# usb_host_slave.net
KiCad netlist of a schematic drawn in Altium Designer
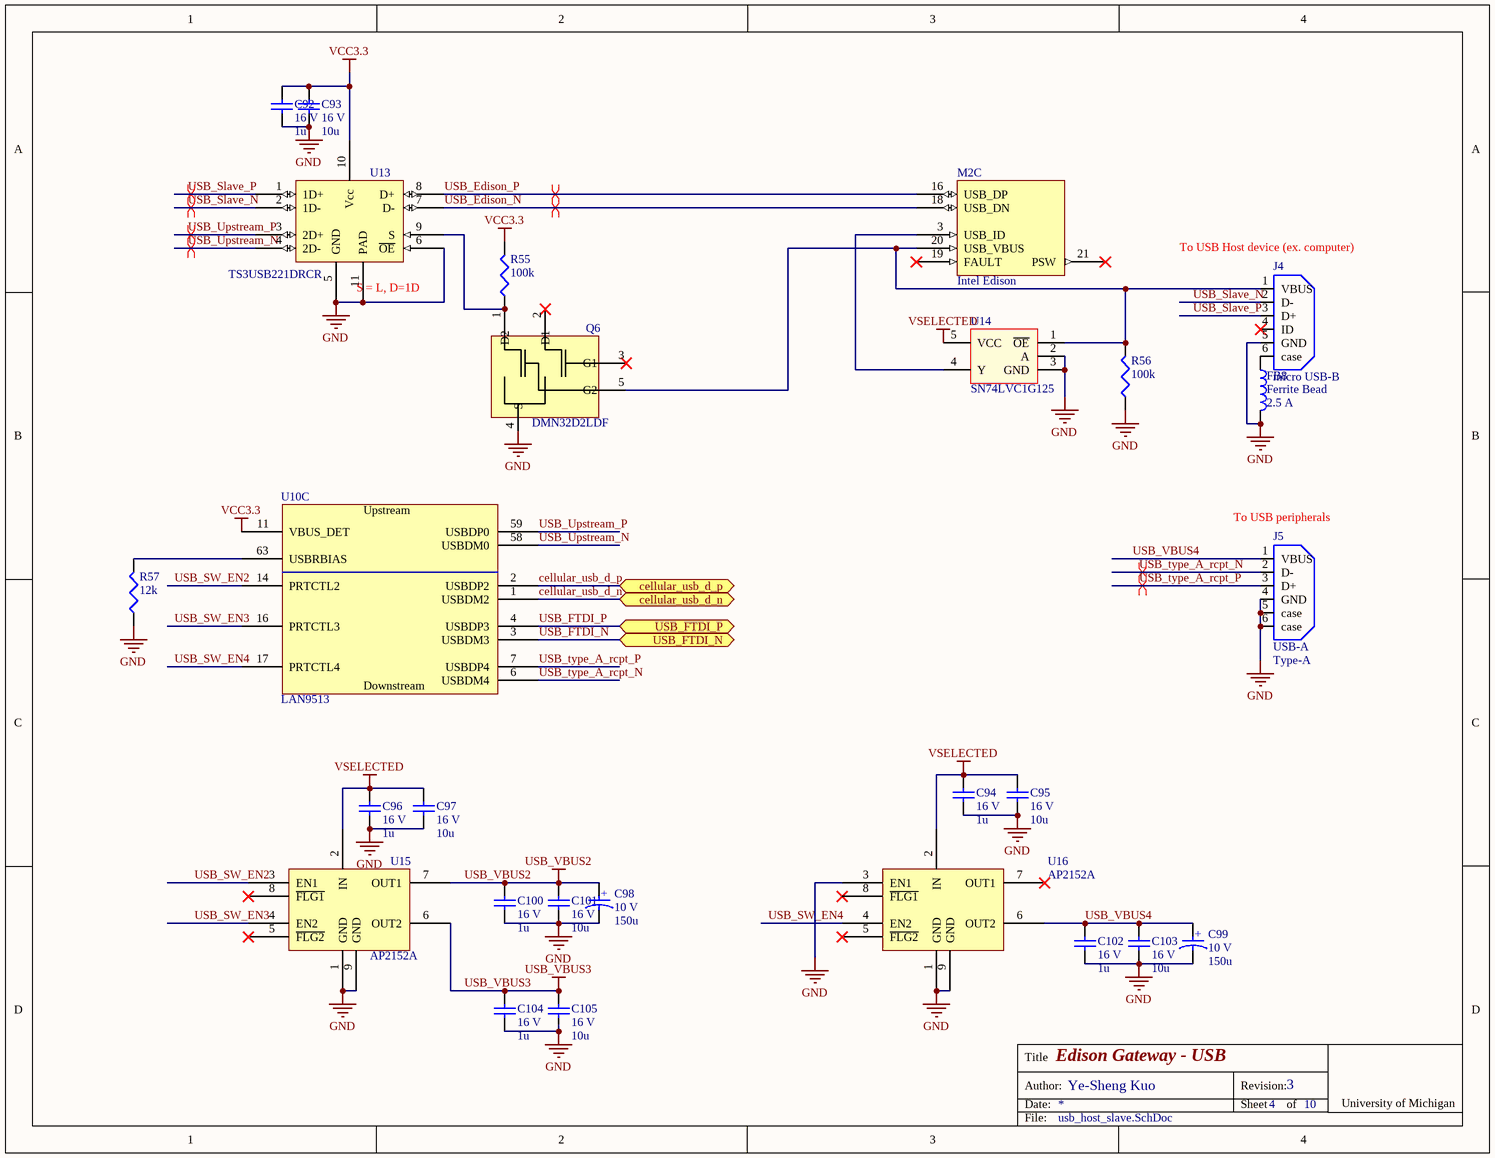
[diagram p0: usb_host_slave.SchDoc]

(export (version "E")
  (design (tool "Eeschema 10.0.6"))
  (components
    (comp (ref "C92")
      (value "1u")
      (footprint "0402")
      (description "1µF ±10% 16V Ceramic Capacitor X6S 0402")
      (fields
        (field (name "VOLTAGE RATED") "16 V")
        (field (name "TOLERANCE") "10%")
        (field (name "MANUFACTURER PART NUMBER") "C1005X6S1C105K050BC")
      )
      (libsource (lib "capacitors") (part "C1005X6S1C105K050BC"))
    )
    (comp (ref "C93")
      (value "10u")
      (footprint "0603")
      (description "10µF ±20% 16V Ceramic Capacitor X6S 0603")
      (fields
        (field (name "TOLERANCE") "20%")
        (field (name "VOLTAGE RATED") "16 V")
        (field (name "MANUFACTURER PART NUMBER") "GRM188C81C106MA73D")
      )
      (libsource (lib "capacitors") (part "GRM188C81C106MA73D"))
    )
    (comp (ref "C94")
      (value "1u")
      (footprint "0402")
      (description "1µF ±10% 16V Ceramic Capacitor X6S 0402")
      (fields
        (field (name "VOLTAGE RATED") "16 V")
        (field (name "TOLERANCE") "10%")
        (field (name "MANUFACTURER PART NUMBER") "C1005X6S1C105K050BC")
      )
      (libsource (lib "capacitors") (part "C1005X6S1C105K050BC"))
    )
    (comp (ref "C95")
      (value "10u")
      (footprint "0603")
      (description "10µF ±20% 16V Ceramic Capacitor X6S 0603")
      (fields
        (field (name "TOLERANCE") "20%")
        (field (name "VOLTAGE RATED") "16 V")
        (field (name "MANUFACTURER PART NUMBER") "GRM188C81C106MA73D")
      )
      (libsource (lib "capacitors") (part "GRM188C81C106MA73D"))
    )
    (comp (ref "C96")
      (value "1u")
      (footprint "0402")
      (description "1µF ±10% 16V Ceramic Capacitor X6S 0402")
      (fields
        (field (name "VOLTAGE RATED") "16 V")
        (field (name "TOLERANCE") "10%")
        (field (name "MANUFACTURER PART NUMBER") "C1005X6S1C105K050BC")
      )
      (libsource (lib "capacitors") (part "C1005X6S1C105K050BC"))
    )
    (comp (ref "C97")
      (value "10u")
      (footprint "0603")
      (description "10µF ±20% 16V Ceramic Capacitor X6S 0603")
      (fields
        (field (name "TOLERANCE") "20%")
        (field (name "VOLTAGE RATED") "16 V")
        (field (name "MANUFACTURER PART NUMBER") "GRM188C81C106MA73D")
      )
      (libsource (lib "capacitors") (part "GRM188C81C106MA73D"))
    )
    (comp (ref "C98")
      (value "150u")
      (footprint "2312")
      (description "150µF ±10% Molded Tantalum Capacitors 10V 2312")
      (fields
        (field (name "TOLERANCE") "10%")
        (field (name "VOLTAGE RATED") "10 V")
        (field (name "MANUFACTURER PART NUMBER") "TAJC157K010RNJ")
      )
      (libsource (lib "capacitors") (part "TAJC157K010RNJ"))
    )
    (comp (ref "C99")
      (value "150u")
      (footprint "2312")
      (description "150µF ±10% Molded Tantalum Capacitors 10V 2312")
      (fields
        (field (name "TOLERANCE") "10%")
        (field (name "VOLTAGE RATED") "10 V")
        (field (name "MANUFACTURER PART NUMBER") "TAJC157K010RNJ")
      )
      (libsource (lib "capacitors") (part "TAJC157K010RNJ"))
    )
    (comp (ref "C100")
      (value "1u")
      (footprint "0402")
      (description "1µF ±10% 16V Ceramic Capacitor X6S 0402")
      (fields
        (field (name "VOLTAGE RATED") "16 V")
        (field (name "TOLERANCE") "10%")
        (field (name "MANUFACTURER PART NUMBER") "C1005X6S1C105K050BC")
      )
      (libsource (lib "capacitors") (part "C1005X6S1C105K050BC"))
    )
    (comp (ref "C101")
      (value "10u")
      (footprint "0603")
      (description "10µF ±20% 16V Ceramic Capacitor X6S 0603")
      (fields
        (field (name "TOLERANCE") "20%")
        (field (name "VOLTAGE RATED") "16 V")
        (field (name "MANUFACTURER PART NUMBER") "GRM188C81C106MA73D")
      )
      (libsource (lib "capacitors") (part "GRM188C81C106MA73D"))
    )
    (comp (ref "C102")
      (value "1u")
      (footprint "0402")
      (description "1µF ±10% 16V Ceramic Capacitor X6S 0402")
      (fields
        (field (name "VOLTAGE RATED") "16 V")
        (field (name "TOLERANCE") "10%")
        (field (name "MANUFACTURER PART NUMBER") "C1005X6S1C105K050BC")
      )
      (libsource (lib "capacitors") (part "C1005X6S1C105K050BC"))
    )
    (comp (ref "C103")
      (value "10u")
      (footprint "0603")
      (description "10µF ±20% 16V Ceramic Capacitor X6S 0603")
      (fields
        (field (name "TOLERANCE") "20%")
        (field (name "VOLTAGE RATED") "16 V")
        (field (name "MANUFACTURER PART NUMBER") "GRM188C81C106MA73D")
      )
      (libsource (lib "capacitors") (part "GRM188C81C106MA73D"))
    )
    (comp (ref "C104")
      (value "1u")
      (footprint "0402")
      (description "1µF ±10% 16V Ceramic Capacitor X6S 0402")
      (fields
        (field (name "VOLTAGE RATED") "16 V")
        (field (name "TOLERANCE") "10%")
        (field (name "MANUFACTURER PART NUMBER") "C1005X6S1C105K050BC")
      )
      (libsource (lib "capacitors") (part "C1005X6S1C105K050BC"))
    )
    (comp (ref "C105")
      (value "10u")
      (footprint "0603")
      (description "10µF ±20% 16V Ceramic Capacitor X6S 0603")
      (fields
        (field (name "TOLERANCE") "20%")
        (field (name "VOLTAGE RATED") "16 V")
        (field (name "MANUFACTURER PART NUMBER") "GRM188C81C106MA73D")
      )
      (libsource (lib "capacitors") (part "GRM188C81C106MA73D"))
    )
    (comp (ref "FB8")
      (value "Ferrite Bead")
      (footprint "0603")
      (description "FERRITE BEAD 220 OHM 0603")
      (fields
        (field (name "MANUFACTURER PART NUMBER") "BLM18SG221TN1D")
        (field (name "MANUFACTURER") "Murata")
        (field (name "CURRENT RATING (MAX)") "2.5 A")
      )
      (libsource (lib "ferrite_beads") (part "BLM18SG221TN1D"))
    )
    (comp (ref "J4")
      (value "micro USB-B")
      (footprint "Micro USB-B")
      (description "CONN USB MICRO B RECPT SMT R/A")
      (libsource (lib "connectors") (part "Micro USB"))
    )
    (comp (ref "J5")
      (value "USB-A")
      (footprint "292303-2")
      (description "USB 2.0 Type A")
      (fields (field (name "TYPE") "Type-A"))
      (libsource (lib "connectors") (part "A105221-ND"))
    )
    (comp (ref "M2")
      (value "Intel Edison")
      (footprint "Intel Edison mating")
      (libsource (lib "Intel Edison") (part "Intel Edison"))
    )
    (comp (ref "Q6")
      (value "DMN32D2LDF")
      (footprint "SOT-353-5")
      (description "Common Source Dual N-Channel MOSFET")
      (libsource (lib "transistors") (part "DMN32D2LDF"))
    )
    (comp (ref "R55")
      (value "100k")
      (footprint "0402")
      (description "RES SMD 100K OHM 1% 1/16W 0402")
      (fields (field (name "TOLERANCE") "1%") (field (name "POWER") "1/16 W"))
      (libsource (lib "resistors") (part "CRCW0402100KFKED"))
    )
    (comp (ref "R56")
      (value "100k")
      (footprint "0402")
      (description "RES SMD 100K OHM 1% 1/16W 0402")
      (fields (field (name "TOLERANCE") "1%") (field (name "POWER") "1/16 W"))
      (libsource (lib "resistors") (part "CRCW0402100KFKED"))
    )
    (comp (ref "R57")
      (value "12k")
      (footprint "0402")
      (description "RES SMD 12K OHM 1% 1/16W 0402")
      (fields (field (name "TOLERANCE") "1%") (field (name "POWER") "1/16 W"))
      (libsource (lib "resistors") (part "CRCW040212K0FKED"))
    )
    (comp (ref "U10")
      (value "LAN9513")
      (footprint "QFN-64")
      (description "USB 2.0 Hub and 10/100  Ethernet Controller")
      (libsource (lib "ethernet controller") (part "LAN9513"))
    )
    (comp (ref "U13")
      (value "TS3USB221DRCR")
      (footprint "S-PVSON-N10")
      (description "High-Speed USB 2.0 (480-Mbps) 1:2 Multiplexer – Demultiplexer  Switch With Single Enable")
      (libsource (lib "multiplexer") (part "TS3USB221DRCR"))
    )
    (comp (ref "U14")
      (value "SN74LVC1G125")
      (footprint "SOT23-5")
      (description "Single Bus Buffer Gate With 3-State Output")
      (libsource (lib "logics") (part "SN74LVC1G125"))
    )
    (comp (ref "U15")
      (value "AP2152A")
      (footprint "U-DFN3030-8")
      (description "0.5A DUAL CHANNEL CURRENT-LIMITED  POWER SWITCH WITH OUTPUT DISCHARGE")
      (libsource (lib "load switch") (part "AP2152A"))
    )
    (comp (ref "U16")
      (value "AP2152A")
      (footprint "U-DFN3030-8")
      (description "0.5A DUAL CHANNEL CURRENT-LIMITED  POWER SWITCH WITH OUTPUT DISCHARGE")
      (libsource (lib "load switch") (part "AP2152A"))
    )
  )
  (nets
    (net (code "1") (name "/USB_Edison_N") (class "Default")
      (node (ref "M2") (pin "18") (pinfunction "USB_DN_18") (pintype "bidirectional"))
      (node (ref "U13") (pin "7") (pinfunction "D-_7") (pintype "bidirectional"))
    )
    (net (code "2") (name "/USB_Edison_P") (class "Default")
      (node (ref "M2") (pin "16") (pinfunction "USB_DP_16") (pintype "bidirectional"))
      (node (ref "U13") (pin "8") (pinfunction "D+_8") (pintype "bidirectional"))
    )
    (net (code "3") (name "/USB_FTDI_N") (class "Default")
      (node (ref "U10") (pin "3") (pinfunction "USBDM3_3") (pintype "passive"))
    )
    (net (code "4") (name "/USB_FTDI_P") (class "Default")
      (node (ref "U10") (pin "4") (pinfunction "USBDP3_4") (pintype "passive"))
    )
    (net (code "5") (name "/USB_SW_EN2") (class "Default")
      (node (ref "U10") (pin "14") (pinfunction "PRTCTL2_14") (pintype "passive"))
      (node (ref "U15") (pin "3") (pinfunction "EN1_3") (pintype "passive"))
    )
    (net (code "6") (name "/USB_SW_EN3") (class "Default")
      (node (ref "U10") (pin "16") (pinfunction "PRTCTL3_16") (pintype "passive"))
      (node (ref "U15") (pin "4") (pinfunction "EN2_4") (pintype "passive"))
    )
    (net (code "7") (name "/USB_SW_EN4") (class "Default")
      (node (ref "U10") (pin "17") (pinfunction "PRTCTL4_17") (pintype "passive"))
      (node (ref "U16") (pin "4") (pinfunction "EN2_4") (pintype "passive"))
    )
    (net (code "8") (name "/USB_Slave_N") (class "Default")
      (node (ref "J4") (pin "2") (pinfunction "D-_2") (pintype "power_in"))
      (node (ref "U13") (pin "2") (pinfunction "1D-_2") (pintype "bidirectional"))
    )
    (net (code "9") (name "/USB_Slave_P") (class "Default")
      (node (ref "J4") (pin "3") (pinfunction "D+_3") (pintype "power_in"))
      (node (ref "U13") (pin "1") (pinfunction "1D+_1") (pintype "bidirectional"))
    )
    (net (code "10") (name "/USB_Upstream_N") (class "Default")
      (node (ref "U10") (pin "58") (pinfunction "USBDM0_58") (pintype "passive"))
      (node (ref "U13") (pin "4") (pinfunction "2D-_4") (pintype "bidirectional"))
    )
    (net (code "11") (name "/USB_Upstream_P") (class "Default")
      (node (ref "U10") (pin "59") (pinfunction "USBDP0_59") (pintype "passive"))
      (node (ref "U13") (pin "3") (pinfunction "2D+_3") (pintype "bidirectional"))
    )
    (net (code "12") (name "/USB_VBUS4") (class "Default")
      (node (ref "C102") (pin "1") (pintype "passive"))
      (node (ref "C103") (pin "1") (pintype "passive"))
      (node (ref "C99") (pin "1") (pintype "passive"))
      (node (ref "J5") (pin "1") (pinfunction "VBUS_1") (pintype "power_in"))
      (node (ref "U16") (pin "6") (pinfunction "OUT2_6") (pintype "passive"))
    )
    (net (code "13") (name "/USB_type_A_rcpt_N") (class "Default")
      (node (ref "J5") (pin "2") (pinfunction "D-_2") (pintype "power_in"))
      (node (ref "U10") (pin "6") (pinfunction "USBDM4_6") (pintype "passive"))
    )
    (net (code "14") (name "/USB_type_A_rcpt_P") (class "Default")
      (node (ref "J5") (pin "3") (pinfunction "D+_3") (pintype "power_in"))
      (node (ref "U10") (pin "7") (pinfunction "USBDP4_7") (pintype "passive"))
    )
    (net (code "15") (name "/cellular_usb_d_n") (class "Default")
      (node (ref "U10") (pin "1") (pinfunction "USBDM2_1") (pintype "passive"))
    )
    (net (code "16") (name "/cellular_usb_d_p") (class "Default")
      (node (ref "U10") (pin "2") (pinfunction "USBDP2_2") (pintype "passive"))
    )
    (net (code "17") (name "GND") (class "Default")
      (node (ref "C100") (pin "2") (pintype "passive"))
      (node (ref "C101") (pin "2") (pintype "passive"))
      (node (ref "C102") (pin "2") (pintype "passive"))
      (node (ref "C103") (pin "2") (pintype "passive"))
      (node (ref "C104") (pin "2") (pintype "passive"))
      (node (ref "C105") (pin "2") (pintype "passive"))
      (node (ref "C92") (pin "2") (pintype "passive"))
      (node (ref "C93") (pin "2") (pintype "passive"))
      (node (ref "C94") (pin "2") (pintype "passive"))
      (node (ref "C95") (pin "2") (pintype "passive"))
      (node (ref "C96") (pin "2") (pintype "passive"))
      (node (ref "C97") (pin "2") (pintype "passive"))
      (node (ref "C98") (pin "2") (pintype "passive"))
      (node (ref "C99") (pin "2") (pintype "passive"))
      (node (ref "FB8") (pin "1") (pintype "passive"))
      (node (ref "J4") (pin "5") (pinfunction "GND_5") (pintype "power_in"))
      (node (ref "J5") (pin "4") (pinfunction "GND_4") (pintype "power_in"))
      (node (ref "J5") (pin "5") (pinfunction "case_5") (pintype "power_in"))
      (node (ref "J5") (pin "6") (pinfunction "case_6") (pintype "power_in"))
      (node (ref "Q6") (pin "4") (pinfunction "S_4") (pintype "passive"))
      (node (ref "R56") (pin "2") (pintype "passive"))
      (node (ref "R57") (pin "2") (pintype "passive"))
      (node (ref "U13") (pin "11") (pinfunction "PAD_11") (pintype "passive"))
      (node (ref "U13") (pin "5") (pinfunction "GND_5") (pintype "passive"))
      (node (ref "U13") (pin "6") (pinfunction "~{OE}_6") (pintype "input"))
      (node (ref "U14") (pin "2") (pinfunction "A_2") (pintype "passive"))
      (node (ref "U14") (pin "3") (pinfunction "GND_3") (pintype "passive"))
      (node (ref "U15") (pin "1") (pinfunction "GND_1") (pintype "passive"))
      (node (ref "U15") (pin "9") (pinfunction "GND_9") (pintype "passive"))
      (node (ref "U16") (pin "1") (pinfunction "GND_1") (pintype "passive"))
      (node (ref "U16") (pin "3") (pinfunction "EN1_3") (pintype "passive"))
      (node (ref "U16") (pin "9") (pinfunction "GND_9") (pintype "passive"))
    )
    (net (code "18") (name "Net-(J4-VBUS)") (class "Default")
      (node (ref "J4") (pin "1") (pinfunction "VBUS_1") (pintype "power_in"))
      (node (ref "M2") (pin "20") (pinfunction "USB_VBUS_20") (pintype "input"))
      (node (ref "Q6") (pin "5") (pinfunction "G2_5") (pintype "passive"))
      (node (ref "R56") (pin "1") (pintype "passive"))
      (node (ref "U14") (pin "1") (pinfunction "~{OE}_1") (pintype "passive"))
    )
    (net (code "19") (name "Net-(J4-case)") (class "Default")
      (node (ref "FB8") (pin "2") (pintype "passive"))
      (node (ref "J4") (pin "6") (pinfunction "case_6") (pintype "power_in"))
    )
    (net (code "20") (name "Net-(M2C-USB_ID)") (class "Default")
      (node (ref "M2") (pin "3") (pinfunction "USB_ID_3") (pintype "input"))
      (node (ref "U14") (pin "4") (pinfunction "Y_4") (pintype "passive"))
    )
    (net (code "21") (name "Net-(Q6-D2)") (class "Default")
      (node (ref "Q6") (pin "1") (pinfunction "D2_1") (pintype "passive"))
      (node (ref "R55") (pin "2") (pintype "passive"))
      (node (ref "U13") (pin "9") (pinfunction "S_9") (pintype "input"))
    )
    (net (code "22") (name "Net-(U10C-USBRBIAS)") (class "Default")
      (node (ref "R57") (pin "1") (pintype "passive"))
      (node (ref "U10") (pin "63") (pinfunction "USBRBIAS_63") (pintype "passive"))
    )
    (net (code "23") (name "USB_VBUS2") (class "Default")
      (node (ref "C100") (pin "1") (pintype "passive"))
      (node (ref "C101") (pin "1") (pintype "passive"))
      (node (ref "C98") (pin "1") (pintype "passive"))
      (node (ref "U15") (pin "7") (pinfunction "OUT1_7") (pintype "passive"))
    )
    (net (code "24") (name "USB_VBUS3") (class "Default")
      (node (ref "C104") (pin "1") (pintype "passive"))
      (node (ref "C105") (pin "1") (pintype "passive"))
      (node (ref "U15") (pin "6") (pinfunction "OUT2_6") (pintype "passive"))
    )
    (net (code "25") (name "VCC3.3") (class "Default")
      (node (ref "C92") (pin "1") (pintype "passive"))
      (node (ref "C93") (pin "1") (pintype "passive"))
      (node (ref "R55") (pin "1") (pintype "passive"))
      (node (ref "U10") (pin "11") (pinfunction "VBUS_DET_11") (pintype "passive"))
      (node (ref "U13") (pin "10") (pinfunction "Vcc_10") (pintype "passive"))
    )
    (net (code "26") (name "VSELECTED") (class "Default")
      (node (ref "C94") (pin "1") (pintype "passive"))
      (node (ref "C95") (pin "1") (pintype "passive"))
      (node (ref "C96") (pin "1") (pintype "passive"))
      (node (ref "C97") (pin "1") (pintype "passive"))
      (node (ref "U14") (pin "5") (pinfunction "VCC_5") (pintype "passive"))
      (node (ref "U15") (pin "2") (pinfunction "IN_2") (pintype "passive"))
      (node (ref "U16") (pin "2") (pinfunction "IN_2") (pintype "passive"))
    )
    (net (code "27") (name "unconnected-(J4-ID-Pad4)") (class "Default")
      (node (ref "J4") (pin "4") (pinfunction "ID_4") (pintype "power_in+no_connect"))
    )
    (net (code "28") (name "unconnected-(M2C-FAULT-Pad19)") (class "Default")
      (node (ref "M2") (pin "19") (pinfunction "FAULT_19") (pintype "input+no_connect"))
    )
    (net (code "29") (name "unconnected-(M2C-PSW-Pad21)") (class "Default")
      (node (ref "M2") (pin "21") (pinfunction "PSW_21") (pintype "output+no_connect"))
    )
    (net (code "30") (name "unconnected-(Q6-D1-Pad2)") (class "Default")
      (node (ref "Q6") (pin "2") (pinfunction "D1_2") (pintype "passive+no_connect"))
    )
    (net (code "31") (name "unconnected-(Q6-G1-Pad3)") (class "Default")
      (node (ref "Q6") (pin "3") (pinfunction "G1_3") (pintype "passive+no_connect"))
    )
    (net (code "32") (name "unconnected-(U15-~{FLG1}-Pad8)") (class "Default")
      (node (ref "U15") (pin "8") (pinfunction "~{FLG1}_8") (pintype "passive+no_connect"))
    )
    (net (code "33") (name "unconnected-(U15-~{FLG2}-Pad5)") (class "Default")
      (node (ref "U15") (pin "5") (pinfunction "~{FLG2}_5") (pintype "passive+no_connect"))
    )
    (net (code "34") (name "unconnected-(U16-OUT1-Pad7)") (class "Default")
      (node (ref "U16") (pin "7") (pinfunction "OUT1_7") (pintype "passive+no_connect"))
    )
    (net (code "35") (name "unconnected-(U16-~{FLG1}-Pad8)") (class "Default")
      (node (ref "U16") (pin "8") (pinfunction "~{FLG1}_8") (pintype "passive+no_connect"))
    )
    (net (code "36") (name "unconnected-(U16-~{FLG2}-Pad5)") (class "Default")
      (node (ref "U16") (pin "5") (pinfunction "~{FLG2}_5") (pintype "passive+no_connect"))
    )
  )
)
